# LDAQ-MOD-4AMPINP.net
KiCad netlist of a schematic drawn in EAGLE
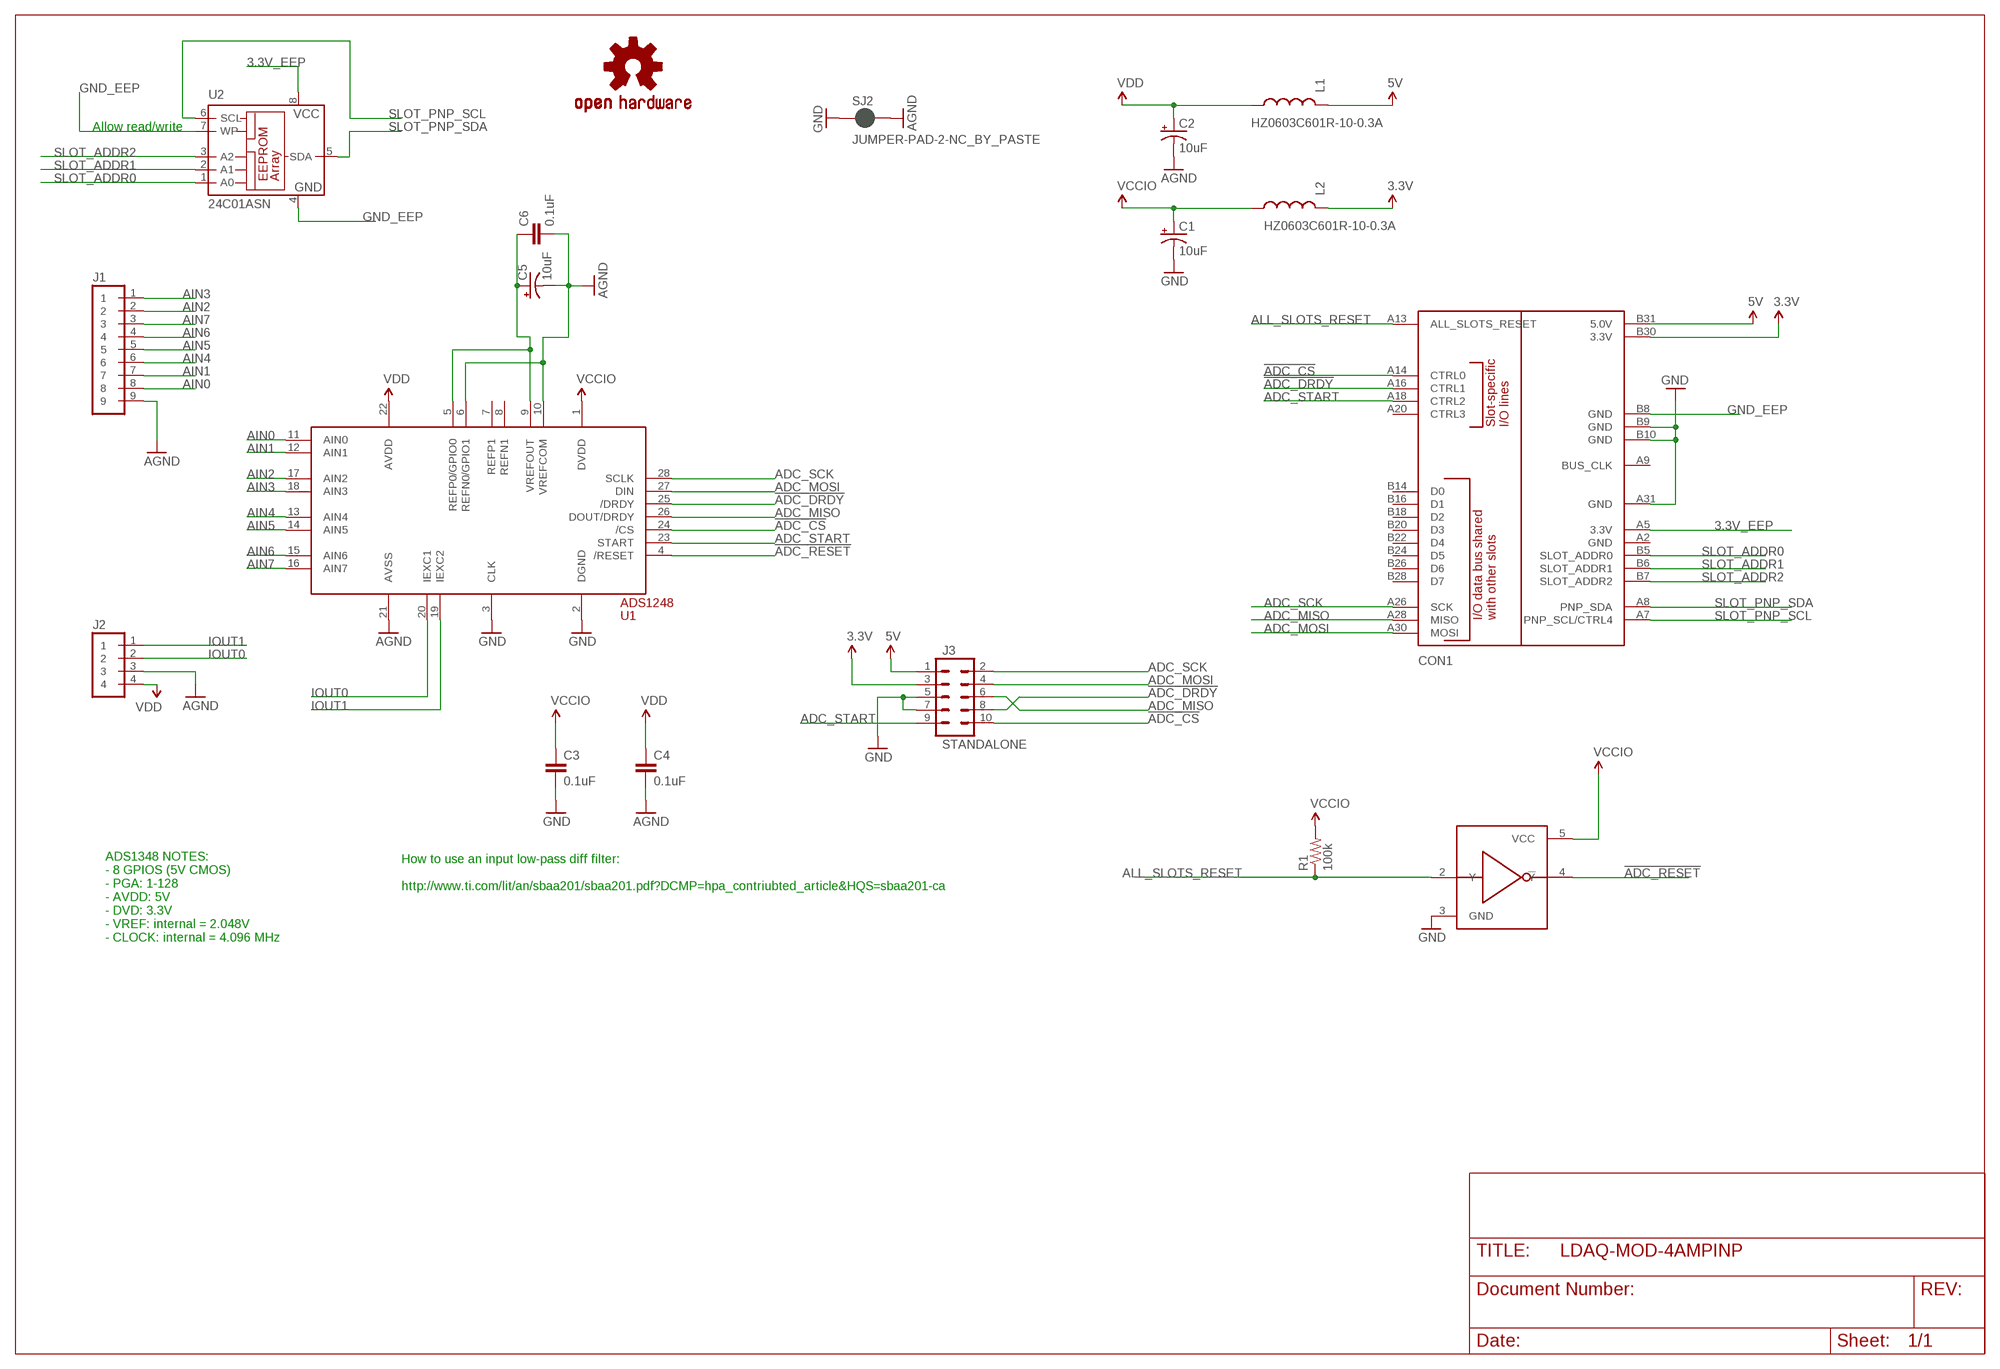
[diagram p0: schematic, sheet 1]

(export (version "E")
  (design (tool "Eeschema 10.0.6"))
  (components
    (comp (ref "C1")
      (value "10uF")
      (footprint "eagle-import:EIA3216")
      (libsource (lib "eagle-import") (part "CAP_POL1206"))
    )
    (comp (ref "C2")
      (value "10uF")
      (footprint "eagle-import:EIA3216")
      (libsource (lib "eagle-import") (part "CAP_POL1206"))
    )
    (comp (ref "C3")
      (value "0.1uF")
      (footprint "eagle-import:0603-CAP")
      (libsource (lib "eagle-import") (part "0.1UF-25V-5%(0603)"))
    )
    (comp (ref "C4")
      (value "0.1uF")
      (footprint "eagle-import:0603-CAP")
      (libsource (lib "eagle-import") (part "0.1UF-25V-5%(0603)"))
    )
    (comp (ref "C5")
      (value "10uF")
      (footprint "eagle-import:EIA3216")
      (libsource (lib "eagle-import") (part "CAP_POL1206"))
    )
    (comp (ref "C6")
      (value "0.1uF")
      (footprint "eagle-import:0603-CAP")
      (libsource (lib "eagle-import") (part "0.1UF-25V-5%(0603)"))
    )
    (comp (ref "CON1")
      (value "BOARD")
      (footprint "eagle-import:PCI-E_64_EDGE_63X50_PADS-ONLY")
      (libsource (lib "eagle-import") (part "LIBREDAQ_DAUGHTER_BOARDPCIE-64-SIZE2-PADS"))
    )
    (comp (ref "J1")
      (value "SCREWTERMINAL-3.5MM-9")
      (footprint "eagle-import:SCREWTERMINAL-3.5MM-9")
      (libsource (lib "eagle-import") (part "SCREWTERMINAL-3.5MM-9"))
    )
    (comp (ref "J2")
      (value "SCREWTERMINAL-3.5MM-4")
      (footprint "eagle-import:SCREWTERMINAL-3.5MM-4")
      (libsource (lib "eagle-import") (part "SCREWTERMINAL-3.5MM-4"))
    )
    (comp (ref "J3")
      (value "STANDALONE")
      (footprint "eagle-import:AVR_ICSP")
      (libsource (lib "eagle-import") (part "M05X2PTH"))
    )
    (comp (ref "L1")
      (value "HZ0603C601R-10-0.3A")
      (footprint "eagle-import:0603")
      (libsource (lib "eagle-import") (part "INDUCTOR0603"))
    )
    (comp (ref "L2")
      (value "HZ0603C601R-10-0.3A")
      (footprint "eagle-import:0603")
      (libsource (lib "eagle-import") (part "INDUCTOR0603"))
    )
    (comp (ref "LOGO1")
      (value "OSHW-LOGOL")
      (footprint "eagle-import:OSHW-LOGO-L")
      (libsource (lib "eagle-import") (part "OSHW-LOGOL"))
    )
    (comp (ref "R1")
      (value "100k")
      (footprint "eagle-import:0603-RES")
      (libsource (lib "eagle-import") (part "100KOHM-1/10W-1%(0603)"))
    )
    (comp (ref "SJ2")
      (value "JUMPER-PAD-2-NC_BY_PASTE")
      (footprint "eagle-import:PAD-JUMPER-2-NC_BY_PASTE_YES_SILK")
      (libsource (lib "eagle-import") (part "JUMPER-PAD-2-NC_BY_PASTE"))
    )
    (comp (ref "U1")
      (value "ADS1248")
      (footprint "eagle-import:TSSOP-28_4MM")
      (libsource (lib "eagle-import") (part "ADS1248"))
    )
    (comp (ref "U2")
      (value "24C01ASN")
      (footprint "eagle-import:SO-08")
      (fields (field (name "MPN") "AT24C01BN-SH-B"))
      (libsource (lib "eagle-import") (part "24CSN01A"))
    )
    (comp (ref "U3")
      (value "74AHCT1G04")
      (footprint "eagle-import:SOT353-SC70-5")
      (libsource (lib "eagle-import") (part "74AHCT1G04"))
    )
  )
  (nets
    (net (code "1") (name "/3.3V_EEP") (class "Default")
      (node (ref "CON1") (pin "A5") (pinfunction "3.3V_A5") (pintype "bidirectional"))
      (node (ref "U2") (pin "8") (pinfunction "VCC_8") (pintype "power_in"))
    )
    (net (code "2") (name "/ADC_MISO") (class "Default")
      (node (ref "CON1") (pin "A28") (pinfunction "MISO_A28") (pintype "bidirectional"))
      (node (ref "J3") (pin "6") (pinfunction "6_6") (pintype "passive"))
      (node (ref "U1") (pin "26") (pinfunction "DOUT/DRDY_26") (pintype "bidirectional"))
    )
    (net (code "3") (name "/ADC_MOSI") (class "Default")
      (node (ref "CON1") (pin "A30") (pinfunction "MOSI_A30") (pintype "bidirectional"))
      (node (ref "J3") (pin "4") (pinfunction "4_4") (pintype "passive"))
      (node (ref "U1") (pin "27") (pinfunction "DIN_27") (pintype "bidirectional"))
    )
    (net (code "4") (name "/ADC_SCK") (class "Default")
      (node (ref "CON1") (pin "A26") (pinfunction "SCK_A26") (pintype "bidirectional"))
      (node (ref "J3") (pin "2") (pinfunction "2_2") (pintype "passive"))
      (node (ref "U1") (pin "28") (pinfunction "SCLK_28") (pintype "bidirectional"))
    )
    (net (code "5") (name "/ADC_START") (class "Default")
      (node (ref "CON1") (pin "A18") (pinfunction "CTRL2_A18") (pintype "bidirectional"))
      (node (ref "J3") (pin "9") (pinfunction "9_9") (pintype "passive"))
      (node (ref "U1") (pin "23") (pinfunction "START_23") (pintype "bidirectional"))
    )
    (net (code "6") (name "/AIN0") (class "Default")
      (node (ref "J1") (pin "8") (pinfunction "8_8") (pintype "bidirectional"))
      (node (ref "U1") (pin "11") (pinfunction "AIN0_11") (pintype "bidirectional"))
    )
    (net (code "7") (name "/AIN1") (class "Default")
      (node (ref "J1") (pin "7") (pinfunction "7_7") (pintype "bidirectional"))
      (node (ref "U1") (pin "12") (pinfunction "AIN1_12") (pintype "bidirectional"))
    )
    (net (code "8") (name "/AIN2") (class "Default")
      (node (ref "J1") (pin "2") (pinfunction "2_2") (pintype "bidirectional"))
      (node (ref "U1") (pin "17") (pinfunction "AIN2_17") (pintype "bidirectional"))
    )
    (net (code "9") (name "/AIN3") (class "Default")
      (node (ref "J1") (pin "1") (pinfunction "1_1") (pintype "bidirectional"))
      (node (ref "U1") (pin "18") (pinfunction "AIN3_18") (pintype "bidirectional"))
    )
    (net (code "10") (name "/AIN4") (class "Default")
      (node (ref "J1") (pin "6") (pinfunction "6_6") (pintype "bidirectional"))
      (node (ref "U1") (pin "13") (pinfunction "AIN4_13") (pintype "bidirectional"))
    )
    (net (code "11") (name "/AIN5") (class "Default")
      (node (ref "J1") (pin "5") (pinfunction "5_5") (pintype "bidirectional"))
      (node (ref "U1") (pin "14") (pinfunction "AIN5_14") (pintype "bidirectional"))
    )
    (net (code "12") (name "/AIN6") (class "Default")
      (node (ref "J1") (pin "4") (pinfunction "4_4") (pintype "bidirectional"))
      (node (ref "U1") (pin "15") (pinfunction "AIN6_15") (pintype "bidirectional"))
    )
    (net (code "13") (name "/AIN7") (class "Default")
      (node (ref "J1") (pin "3") (pinfunction "3_3") (pintype "bidirectional"))
      (node (ref "U1") (pin "16") (pinfunction "AIN7_16") (pintype "bidirectional"))
    )
    (net (code "14") (name "/ALL_SLOTS_RESET") (class "Default")
      (node (ref "CON1") (pin "A13") (pinfunction "ALL_SLOTS_RESET_A13") (pintype "bidirectional"))
      (node (ref "R1") (pin "1") (pinfunction "1_1") (pintype "passive"))
      (node (ref "U3") (pin "2") (pinfunction "Y_2") (pintype "bidirectional"))
    )
    (net (code "15") (name "/GND_EEP") (class "Default")
      (node (ref "CON1") (pin "B8") (pinfunction "GND_B8") (pintype "bidirectional"))
      (node (ref "U2") (pin "4") (pinfunction "GND_4") (pintype "power_in"))
      (node (ref "U2") (pin "7") (pinfunction "WP_7") (pintype "input"))
    )
    (net (code "16") (name "/IOUT0") (class "Default")
      (node (ref "J2") (pin "2") (pinfunction "2_2") (pintype "bidirectional"))
      (node (ref "U1") (pin "20") (pinfunction "IEXC1_20") (pintype "bidirectional"))
    )
    (net (code "17") (name "/IOUT1") (class "Default")
      (node (ref "J2") (pin "1") (pinfunction "1_1") (pintype "bidirectional"))
      (node (ref "U1") (pin "19") (pinfunction "IEXC2_19") (pintype "bidirectional"))
    )
    (net (code "18") (name "/SLOT_ADDR0") (class "Default")
      (node (ref "CON1") (pin "B5") (pinfunction "SLOT_ADDR0_B5") (pintype "bidirectional"))
      (node (ref "U2") (pin "1") (pinfunction "A0_1") (pintype "input"))
    )
    (net (code "19") (name "/SLOT_ADDR1") (class "Default")
      (node (ref "CON1") (pin "B6") (pinfunction "SLOT_ADDR1_B6") (pintype "bidirectional"))
      (node (ref "U2") (pin "2") (pinfunction "A1_2") (pintype "input"))
    )
    (net (code "20") (name "/SLOT_ADDR2") (class "Default")
      (node (ref "CON1") (pin "B7") (pinfunction "SLOT_ADDR2_B7") (pintype "bidirectional"))
      (node (ref "U2") (pin "3") (pinfunction "A2_3") (pintype "input"))
    )
    (net (code "21") (name "/SLOT_PNP_SCL") (class "Default")
      (node (ref "CON1") (pin "A7") (pinfunction "PNP_SCL/CTRL4_A7") (pintype "bidirectional"))
      (node (ref "U2") (pin "6") (pinfunction "SCL_6") (pintype "input"))
    )
    (net (code "22") (name "/SLOT_PNP_SDA") (class "Default")
      (node (ref "CON1") (pin "A8") (pinfunction "PNP_SDA_A8") (pintype "bidirectional"))
      (node (ref "U2") (pin "5") (pinfunction "SDA_5") (pintype "bidirectional"))
    )
    (net (code "23") (name "/~{ADC_CS}") (class "Default")
      (node (ref "CON1") (pin "A14") (pinfunction "CTRL0_A14") (pintype "bidirectional"))
      (node (ref "J3") (pin "10") (pinfunction "10_10") (pintype "passive"))
      (node (ref "U1") (pin "24") (pinfunction "/CS_24") (pintype "bidirectional"))
    )
    (net (code "24") (name "/~{ADC_DRDY}") (class "Default")
      (node (ref "CON1") (pin "A16") (pinfunction "CTRL1_A16") (pintype "bidirectional"))
      (node (ref "J3") (pin "8") (pinfunction "8_8") (pintype "passive"))
      (node (ref "U1") (pin "25") (pinfunction "/DRDY_25") (pintype "bidirectional"))
    )
    (net (code "25") (name "/~{ADC_RESET}") (class "Default")
      (node (ref "U1") (pin "4") (pinfunction "/RESET_4") (pintype "bidirectional"))
      (node (ref "U3") (pin "4") (pinfunction "~{Y}_4") (pintype "bidirectional"))
    )
    (net (code "26") (name "3.3V") (class "Default")
      (node (ref "CON1") (pin "B30") (pinfunction "3.3V_B30") (pintype "bidirectional"))
      (node (ref "J3") (pin "3") (pinfunction "3_3") (pintype "passive"))
      (node (ref "L2") (pin "1") (pinfunction "1_1") (pintype "passive"))
    )
    (net (code "27") (name "5V") (class "Default")
      (node (ref "CON1") (pin "B31") (pinfunction "5.0V_B31") (pintype "bidirectional"))
      (node (ref "J3") (pin "1") (pinfunction "1_1") (pintype "passive"))
      (node (ref "L1") (pin "1") (pinfunction "1_1") (pintype "passive"))
    )
    (net (code "28") (name "AGND") (class "Default")
      (node (ref "C2") (pin "C") (pinfunction "-_C") (pintype "passive"))
      (node (ref "C4") (pin "2") (pinfunction "2_2") (pintype "passive"))
      (node (ref "C5") (pin "C") (pinfunction "-_C") (pintype "passive"))
      (node (ref "C6") (pin "2") (pinfunction "2_2") (pintype "passive"))
      (node (ref "J1") (pin "9") (pinfunction "9_9") (pintype "bidirectional"))
      (node (ref "J2") (pin "3") (pinfunction "3_3") (pintype "bidirectional"))
      (node (ref "SJ2") (pin "2") (pinfunction "2_2") (pintype "passive"))
      (node (ref "U1") (pin "10") (pinfunction "VREFCOM_10") (pintype "bidirectional"))
      (node (ref "U1") (pin "21") (pinfunction "AVSS_21") (pintype "bidirectional"))
      (node (ref "U1") (pin "6") (pinfunction "REFN0/GPIO1_6") (pintype "bidirectional"))
    )
    (net (code "29") (name "GND") (class "Default")
      (node (ref "C1") (pin "C") (pinfunction "-_C") (pintype "passive"))
      (node (ref "C3") (pin "2") (pinfunction "2_2") (pintype "passive"))
      (node (ref "CON1") (pin "A31") (pinfunction "GND_A31") (pintype "bidirectional"))
      (node (ref "CON1") (pin "B10") (pinfunction "GND_B10") (pintype "bidirectional"))
      (node (ref "CON1") (pin "B9") (pinfunction "GND_B9") (pintype "bidirectional"))
      (node (ref "J3") (pin "5") (pinfunction "5_5") (pintype "passive"))
      (node (ref "J3") (pin "7") (pinfunction "7_7") (pintype "passive"))
      (node (ref "SJ2") (pin "1") (pinfunction "1_1") (pintype "passive"))
      (node (ref "U1") (pin "2") (pinfunction "DGND_2") (pintype "bidirectional"))
      (node (ref "U1") (pin "3") (pinfunction "CLK_3") (pintype "bidirectional"))
      (node (ref "U3") (pin "3") (pinfunction "GND_3") (pintype "bidirectional"))
    )
    (net (code "30") (name "Net-(C5-+)") (class "Default")
      (node (ref "C5") (pin "A") (pinfunction "+_A") (pintype "passive"))
      (node (ref "C6") (pin "1") (pinfunction "1_1") (pintype "passive"))
      (node (ref "U1") (pin "5") (pinfunction "REFP0/GPIO0_5") (pintype "bidirectional"))
      (node (ref "U1") (pin "9") (pinfunction "VREFOUT_9") (pintype "bidirectional"))
    )
    (net (code "31") (name "VCCIO") (class "Default")
      (node (ref "C1") (pin "A") (pinfunction "+_A") (pintype "passive"))
      (node (ref "C3") (pin "1") (pinfunction "1_1") (pintype "passive"))
      (node (ref "L2") (pin "2") (pinfunction "2_2") (pintype "passive"))
      (node (ref "R1") (pin "2") (pinfunction "2_2") (pintype "passive"))
      (node (ref "U1") (pin "1") (pinfunction "DVDD_1") (pintype "bidirectional"))
      (node (ref "U3") (pin "5") (pinfunction "VCC_5") (pintype "bidirectional"))
    )
    (net (code "32") (name "VDD") (class "Default")
      (node (ref "C2") (pin "A") (pinfunction "+_A") (pintype "passive"))
      (node (ref "C4") (pin "1") (pinfunction "1_1") (pintype "passive"))
      (node (ref "J2") (pin "4") (pinfunction "4_4") (pintype "bidirectional"))
      (node (ref "L1") (pin "2") (pinfunction "2_2") (pintype "passive"))
      (node (ref "U1") (pin "22") (pinfunction "AVDD_22") (pintype "bidirectional"))
    )
    (net (code "33") (name "unconnected-(CON1-BUS_CLK-PadA9)") (class "Default")
      (node (ref "CON1") (pin "A9") (pinfunction "BUS_CLK_A9") (pintype "bidirectional"))
    )
    (net (code "34") (name "unconnected-(CON1-CTRL3-PadA20)") (class "Default")
      (node (ref "CON1") (pin "A20") (pinfunction "CTRL3_A20") (pintype "bidirectional"))
    )
    (net (code "35") (name "unconnected-(CON1-D0-PadB14)") (class "Default")
      (node (ref "CON1") (pin "B14") (pinfunction "D0_B14") (pintype "bidirectional"))
    )
    (net (code "36") (name "unconnected-(CON1-D1-PadB16)") (class "Default")
      (node (ref "CON1") (pin "B16") (pinfunction "D1_B16") (pintype "bidirectional"))
    )
    (net (code "37") (name "unconnected-(CON1-D2-PadB18)") (class "Default")
      (node (ref "CON1") (pin "B18") (pinfunction "D2_B18") (pintype "bidirectional"))
    )
    (net (code "38") (name "unconnected-(CON1-D3-PadB20)") (class "Default")
      (node (ref "CON1") (pin "B20") (pinfunction "D3_B20") (pintype "bidirectional"))
    )
    (net (code "39") (name "unconnected-(CON1-D4-PadB22)") (class "Default")
      (node (ref "CON1") (pin "B22") (pinfunction "D4_B22") (pintype "bidirectional"))
    )
    (net (code "40") (name "unconnected-(CON1-D5-PadB24)") (class "Default")
      (node (ref "CON1") (pin "B24") (pinfunction "D5_B24") (pintype "bidirectional"))
    )
    (net (code "41") (name "unconnected-(CON1-D6-PadB26)") (class "Default")
      (node (ref "CON1") (pin "B26") (pinfunction "D6_B26") (pintype "bidirectional"))
    )
    (net (code "42") (name "unconnected-(CON1-D7-PadB28)") (class "Default")
      (node (ref "CON1") (pin "B28") (pinfunction "D7_B28") (pintype "bidirectional"))
    )
    (net (code "43") (name "unconnected-(CON1-GND-PadA2)") (class "Default")
      (node (ref "CON1") (pin "A2") (pinfunction "GND_A2") (pintype "bidirectional"))
    )
    (net (code "44") (name "unconnected-(U1-REFN1-Pad8)") (class "Default")
      (node (ref "U1") (pin "8") (pinfunction "REFN1_8") (pintype "bidirectional"))
    )
    (net (code "45") (name "unconnected-(U1-REFP1-Pad7)") (class "Default")
      (node (ref "U1") (pin "7") (pinfunction "REFP1_7") (pintype "bidirectional"))
    )
  )
)
